# smart-switch.net
KiCad netlist of a schematic drawn in Altium Designer
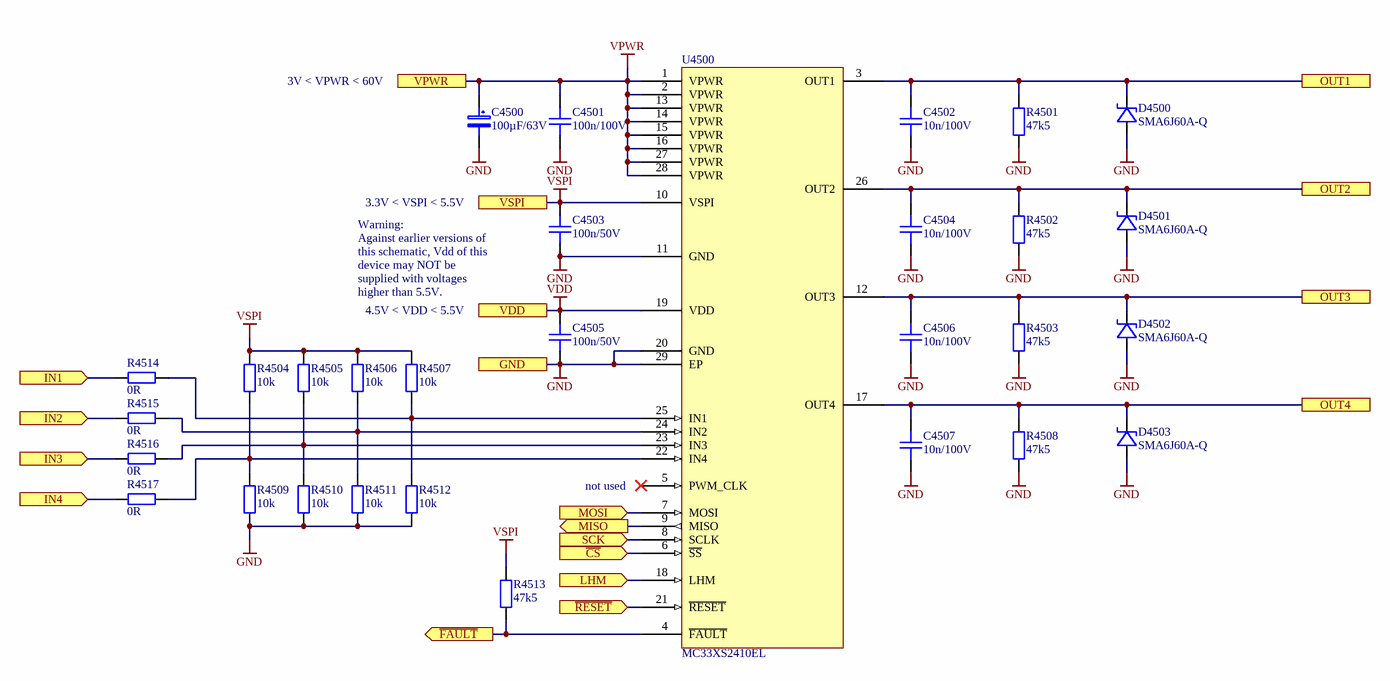
[diagram p0: smart-switch.SchDoc]

(export (version "E")
  (design (tool "Eeschema 10.0.6"))
  (components
    (comp (ref "C4500")
      (value "100µF/63V")
      (footprint "ELECTROLYTIC_CAP_PANASONIC_G")
      (description "SMD Electrolytic Capacitor")
      (fields (field (name "PART NUMBER") "EEE-TG1J101UP") (field (name "TOLERANCE") "+-20%"))
      (libsource (lib "OE750") (part "C_Pol"))
    )
    (comp (ref "C4501")
      (value "100n/100V")
      (footprint "CAPC1608X08N")
      (description "MLCC")
      (fields (field (name "PART NUMBER") "gen_C_ceramic_100n_100V_X7R_0603"))
      (libsource (lib "OE750") (part "C"))
    )
    (comp (ref "C4502")
      (value "10n/100V")
      (footprint "CAPC1608X08N")
      (description "MLCC")
      (fields (field (name "PART NUMBER") "gen_C_ceramic_10n_100V_X7R_0603"))
      (libsource (lib "OE750") (part "C"))
    )
    (comp (ref "C4503")
      (value "100n/50V")
      (footprint "CAPC1005X06N")
      (description "MLCC")
      (fields (field (name "PART NUMBER") "gen_C_ceramic_100n_50V_X7R_0402"))
      (libsource (lib "OE750") (part "C"))
    )
    (comp (ref "C4504")
      (value "10n/100V")
      (footprint "CAPC1608X08N")
      (description "MLCC")
      (fields (field (name "PART NUMBER") "gen_C_ceramic_10n_100V_X7R_0603"))
      (libsource (lib "OE750") (part "C"))
    )
    (comp (ref "C4505")
      (value "100n/50V")
      (footprint "CAPC1005X06N")
      (description "MLCC")
      (fields (field (name "PART NUMBER") "gen_C_ceramic_100n_50V_X7R_0402"))
      (libsource (lib "OE750") (part "C"))
    )
    (comp (ref "C4506")
      (value "10n/100V")
      (footprint "CAPC1608X08N")
      (description "MLCC")
      (fields (field (name "PART NUMBER") "gen_C_ceramic_10n_100V_X7R_0603"))
      (libsource (lib "OE750") (part "C"))
    )
    (comp (ref "C4507")
      (value "10n/100V")
      (footprint "CAPC1608X08N")
      (description "MLCC")
      (fields (field (name "PART NUMBER") "gen_C_ceramic_10n_100V_X7R_0603"))
      (libsource (lib "OE750") (part "C"))
    )
    (comp (ref "D4500")
      (value "SMA6J60A-Q")
      (footprint "BOURNS_DO-214AC_SMA")
      (description "TVS-Diode DO-214AC (SMA)")
      (fields (field (name "MANUFACTURER") "Bourns"))
      (libsource (lib "OE750") (part "D_TVS"))
    )
    (comp (ref "D4501")
      (value "SMA6J60A-Q")
      (footprint "BOURNS_DO-214AC_SMA")
      (description "TVS-Diode DO-214AC (SMA)")
      (fields (field (name "MANUFACTURER") "Bourns"))
      (libsource (lib "OE750") (part "D_TVS"))
    )
    (comp (ref "D4502")
      (value "SMA6J60A-Q")
      (footprint "BOURNS_DO-214AC_SMA")
      (description "TVS-Diode DO-214AC (SMA)")
      (fields (field (name "MANUFACTURER") "Bourns"))
      (libsource (lib "OE750") (part "D_TVS"))
    )
    (comp (ref "D4503")
      (value "SMA6J60A-Q")
      (footprint "BOURNS_DO-214AC_SMA")
      (description "TVS-Diode DO-214AC (SMA)")
      (fields (field (name "MANUFACTURER") "Bourns"))
      (libsource (lib "OE750") (part "D_TVS"))
    )
    (comp (ref "R4501")
      (value "47k5")
      (footprint "RESC1005X04N")
      (description "SMD Resistor 47k5 0402")
      (fields (field (name "PART NUMBER") "gen_R_47k5_0402") (field (name "TOLERANCE") "1%"))
      (libsource (lib "OE750") (part "R"))
    )
    (comp (ref "R4502")
      (value "47k5")
      (footprint "RESC1005X04N")
      (description "SMD Resistor 47k5 0402")
      (fields (field (name "PART NUMBER") "gen_R_47k5_0402") (field (name "TOLERANCE") "1%"))
      (libsource (lib "OE750") (part "R"))
    )
    (comp (ref "R4503")
      (value "47k5")
      (footprint "RESC1005X04N")
      (description "SMD Resistor 47k5 0402")
      (fields (field (name "PART NUMBER") "gen_R_47k5_0402") (field (name "TOLERANCE") "1%"))
      (libsource (lib "OE750") (part "R"))
    )
    (comp (ref "R4504")
      (value "10k")
      (footprint "RESC1005X04N")
      (description "SMD Resistor 10k 0402")
      (fields (field (name "PART NUMBER") "gen_R_10k_0402") (field (name "TOLERANCE") "1%"))
      (libsource (lib "OE750") (part "R"))
    )
    (comp (ref "R4505")
      (value "10k")
      (footprint "RESC1005X04N")
      (description "SMD Resistor 10k 0402")
      (fields (field (name "PART NUMBER") "gen_R_10k_0402") (field (name "TOLERANCE") "1%"))
      (libsource (lib "OE750") (part "R"))
    )
    (comp (ref "R4506")
      (value "10k")
      (footprint "RESC1005X04N")
      (description "SMD Resistor 10k 0402")
      (fields (field (name "PART NUMBER") "gen_R_10k_0402") (field (name "TOLERANCE") "1%"))
      (libsource (lib "OE750") (part "R"))
    )
    (comp (ref "R4507")
      (value "10k")
      (footprint "RESC1005X04N")
      (description "SMD Resistor 10k 0402")
      (fields (field (name "PART NUMBER") "gen_R_10k_0402") (field (name "TOLERANCE") "1%"))
      (libsource (lib "OE750") (part "R"))
    )
    (comp (ref "R4508")
      (value "47k5")
      (footprint "RESC1005X04N")
      (description "SMD Resistor 47k5 0402")
      (fields (field (name "PART NUMBER") "gen_R_47k5_0402") (field (name "TOLERANCE") "1%"))
      (libsource (lib "OE750") (part "R"))
    )
    (comp (ref "R4509")
      (value "10k")
      (footprint "RESC1005X04N")
      (description "SMD Resistor 10k 0402")
      (fields (field (name "PART NUMBER") "gen_R_10k_0402") (field (name "TOLERANCE") "1%"))
      (libsource (lib "OE750") (part "R"))
    )
    (comp (ref "R4510")
      (value "10k")
      (footprint "RESC1005X04N")
      (description "SMD Resistor 10k 0402")
      (fields (field (name "PART NUMBER") "gen_R_10k_0402") (field (name "TOLERANCE") "1%"))
      (libsource (lib "OE750") (part "R"))
    )
    (comp (ref "R4511")
      (value "10k")
      (footprint "RESC1005X04N")
      (description "SMD Resistor 10k 0402")
      (fields (field (name "PART NUMBER") "gen_R_10k_0402") (field (name "TOLERANCE") "1%"))
      (libsource (lib "OE750") (part "R"))
    )
    (comp (ref "R4512")
      (value "10k")
      (footprint "RESC1005X04N")
      (description "SMD Resistor 10k 0402")
      (fields (field (name "PART NUMBER") "gen_R_10k_0402") (field (name "TOLERANCE") "1%"))
      (libsource (lib "OE750") (part "R"))
    )
    (comp (ref "R4513")
      (value "47k5")
      (footprint "RESC1005X04N")
      (description "SMD Resistor 47k5 0402")
      (fields (field (name "PART NUMBER") "gen_R_47k5_0402") (field (name "TOLERANCE") "1%"))
      (libsource (lib "OE750") (part "R"))
    )
    (comp (ref "R4514")
      (value "0R")
      (footprint "RESC1005X04N")
      (description "SMD Resistor 0R 0402")
      (fields (field (name "PART NUMBER") "gen_R_0R_0402") (field (name "POWER") "0.063W"))
      (libsource (lib "OE750") (part "R"))
    )
    (comp (ref "R4515")
      (value "0R")
      (footprint "RESC1005X04N")
      (description "SMD Resistor 0R 0402")
      (fields (field (name "PART NUMBER") "gen_R_0R_0402") (field (name "POWER") "0.063W"))
      (libsource (lib "OE750") (part "R"))
    )
    (comp (ref "R4516")
      (value "0R")
      (footprint "RESC1005X04N")
      (description "SMD Resistor 0R 0402")
      (fields (field (name "PART NUMBER") "gen_R_0R_0402") (field (name "POWER") "0.063W"))
      (libsource (lib "OE750") (part "R"))
    )
    (comp (ref "R4517")
      (value "0R")
      (footprint "RESC1005X04N")
      (description "SMD Resistor 0R 0402")
      (fields (field (name "PART NUMBER") "gen_R_0R_0402") (field (name "POWER") "0.063W"))
      (libsource (lib "OE750") (part "R"))
    )
    (comp (ref "U4500")
      (value "MC33XS2410EL")
      (footprint "MC33XS2410EL")
      (description "Quad 100 mΩ / dual 50 mΩ, 3.0 V to 60 V high-side switch")
      (fields (field (name "MANUFACTURER") "NXP"))
      (libsource (lib "OE750") (part "MC33XS2410EL"))
    )
  )
  (nets
    (net (code "1") (name "/CS") (class "Default")
      (node (ref "U4500") (pin "6") (pinfunction "SS_6") (pintype "input"))
    )
    (net (code "2") (name "/FAULT") (class "Default")
      (node (ref "R4513") (pin "1") (pinfunction "1_1") (pintype "passive"))
      (node (ref "U4500") (pin "4") (pinfunction "FAULT_4") (pintype "open_collector"))
    )
    (net (code "3") (name "/IN1") (class "Default")
      (node (ref "R4514") (pin "1") (pinfunction "1_1") (pintype "passive"))
    )
    (net (code "4") (name "/IN2") (class "Default")
      (node (ref "R4515") (pin "1") (pinfunction "1_1") (pintype "passive"))
    )
    (net (code "5") (name "/IN3") (class "Default")
      (node (ref "R4516") (pin "1") (pinfunction "1_1") (pintype "passive"))
    )
    (net (code "6") (name "/IN4") (class "Default")
      (node (ref "R4517") (pin "1") (pinfunction "1_1") (pintype "passive"))
    )
    (net (code "7") (name "/LHM") (class "Default")
      (node (ref "U4500") (pin "18") (pinfunction "LHM_18") (pintype "input"))
    )
    (net (code "8") (name "/MISO") (class "Default")
      (node (ref "U4500") (pin "9") (pinfunction "MISO_9") (pintype "output"))
    )
    (net (code "9") (name "/MOSI") (class "Default")
      (node (ref "U4500") (pin "7") (pinfunction "MOSI_7") (pintype "input"))
    )
    (net (code "10") (name "/OUT1") (class "Default")
      (node (ref "C4502") (pin "2") (pinfunction "2_2") (pintype "passive"))
      (node (ref "D4500") (pin "1") (pinfunction "C_1") (pintype "passive"))
      (node (ref "R4501") (pin "2") (pinfunction "2_2") (pintype "passive"))
      (node (ref "U4500") (pin "3") (pinfunction "OUT1_3") (pintype "power_in"))
    )
    (net (code "11") (name "/OUT2") (class "Default")
      (node (ref "C4504") (pin "2") (pinfunction "2_2") (pintype "passive"))
      (node (ref "D4501") (pin "1") (pinfunction "C_1") (pintype "passive"))
      (node (ref "R4502") (pin "2") (pinfunction "2_2") (pintype "passive"))
      (node (ref "U4500") (pin "26") (pinfunction "OUT2_26") (pintype "power_in"))
    )
    (net (code "12") (name "/OUT3") (class "Default")
      (node (ref "C4506") (pin "2") (pinfunction "2_2") (pintype "passive"))
      (node (ref "D4502") (pin "1") (pinfunction "C_1") (pintype "passive"))
      (node (ref "R4503") (pin "2") (pinfunction "2_2") (pintype "passive"))
      (node (ref "U4500") (pin "12") (pinfunction "OUT3_12") (pintype "power_in"))
    )
    (net (code "13") (name "/OUT4") (class "Default")
      (node (ref "C4507") (pin "2") (pinfunction "2_2") (pintype "passive"))
      (node (ref "D4503") (pin "1") (pinfunction "C_1") (pintype "passive"))
      (node (ref "R4508") (pin "2") (pinfunction "2_2") (pintype "passive"))
      (node (ref "U4500") (pin "17") (pinfunction "OUT4_17") (pintype "power_in"))
    )
    (net (code "14") (name "/RESET") (class "Default")
      (node (ref "U4500") (pin "21") (pinfunction "RESET_21") (pintype "input"))
    )
    (net (code "15") (name "/SCK") (class "Default")
      (node (ref "U4500") (pin "8") (pinfunction "SCLK_8") (pintype "input"))
    )
    (net (code "16") (name "GND") (class "Default")
      (node (ref "C4500") (pin "2") (pinfunction "2_2") (pintype "passive"))
      (node (ref "C4501") (pin "1") (pinfunction "1_1") (pintype "passive"))
      (node (ref "C4502") (pin "1") (pinfunction "1_1") (pintype "passive"))
      (node (ref "C4503") (pin "1") (pinfunction "1_1") (pintype "passive"))
      (node (ref "C4504") (pin "1") (pinfunction "1_1") (pintype "passive"))
      (node (ref "C4505") (pin "1") (pinfunction "1_1") (pintype "passive"))
      (node (ref "C4506") (pin "1") (pinfunction "1_1") (pintype "passive"))
      (node (ref "C4507") (pin "1") (pinfunction "1_1") (pintype "passive"))
      (node (ref "D4500") (pin "2") (pinfunction "A_2") (pintype "passive"))
      (node (ref "D4501") (pin "2") (pinfunction "A_2") (pintype "passive"))
      (node (ref "D4502") (pin "2") (pinfunction "A_2") (pintype "passive"))
      (node (ref "D4503") (pin "2") (pinfunction "A_2") (pintype "passive"))
      (node (ref "R4501") (pin "1") (pinfunction "1_1") (pintype "passive"))
      (node (ref "R4502") (pin "1") (pinfunction "1_1") (pintype "passive"))
      (node (ref "R4503") (pin "1") (pinfunction "1_1") (pintype "passive"))
      (node (ref "R4508") (pin "1") (pinfunction "1_1") (pintype "passive"))
      (node (ref "R4509") (pin "1") (pinfunction "1_1") (pintype "passive"))
      (node (ref "R4510") (pin "1") (pinfunction "1_1") (pintype "passive"))
      (node (ref "R4511") (pin "1") (pinfunction "1_1") (pintype "passive"))
      (node (ref "R4512") (pin "1") (pinfunction "1_1") (pintype "passive"))
      (node (ref "U4500") (pin "11") (pinfunction "GND_11") (pintype "power_in"))
      (node (ref "U4500") (pin "20") (pinfunction "GND_20") (pintype "power_in"))
      (node (ref "U4500") (pin "29") (pinfunction "EP_29") (pintype "power_in"))
    )
    (net (code "17") (name "Net-(U4500-IN1)") (class "Default")
      (node (ref "R4507") (pin "1") (pinfunction "1_1") (pintype "passive"))
      (node (ref "R4512") (pin "2") (pinfunction "2_2") (pintype "passive"))
      (node (ref "R4514") (pin "2") (pinfunction "2_2") (pintype "passive"))
      (node (ref "U4500") (pin "25") (pinfunction "IN1_25") (pintype "input"))
    )
    (net (code "18") (name "Net-(U4500-IN2)") (class "Default")
      (node (ref "R4506") (pin "1") (pinfunction "1_1") (pintype "passive"))
      (node (ref "R4511") (pin "2") (pinfunction "2_2") (pintype "passive"))
      (node (ref "R4515") (pin "2") (pinfunction "2_2") (pintype "passive"))
      (node (ref "U4500") (pin "24") (pinfunction "IN2_24") (pintype "input"))
    )
    (net (code "19") (name "Net-(U4500-IN3)") (class "Default")
      (node (ref "R4505") (pin "1") (pinfunction "1_1") (pintype "passive"))
      (node (ref "R4510") (pin "2") (pinfunction "2_2") (pintype "passive"))
      (node (ref "R4516") (pin "2") (pinfunction "2_2") (pintype "passive"))
      (node (ref "U4500") (pin "23") (pinfunction "IN3_23") (pintype "input"))
    )
    (net (code "20") (name "Net-(U4500-IN4)") (class "Default")
      (node (ref "R4504") (pin "1") (pinfunction "1_1") (pintype "passive"))
      (node (ref "R4509") (pin "2") (pinfunction "2_2") (pintype "passive"))
      (node (ref "R4517") (pin "2") (pinfunction "2_2") (pintype "passive"))
      (node (ref "U4500") (pin "22") (pinfunction "IN4_22") (pintype "input"))
    )
    (net (code "21") (name "VDD") (class "Default")
      (node (ref "C4505") (pin "2") (pinfunction "2_2") (pintype "passive"))
      (node (ref "U4500") (pin "19") (pinfunction "VDD_19") (pintype "power_in"))
    )
    (net (code "22") (name "VPWR") (class "Default")
      (node (ref "C4500") (pin "1") (pinfunction "1_1") (pintype "passive"))
      (node (ref "C4501") (pin "2") (pinfunction "2_2") (pintype "passive"))
      (node (ref "U4500") (pin "1") (pinfunction "VPWR_1") (pintype "power_in"))
      (node (ref "U4500") (pin "13") (pinfunction "VPWR_13") (pintype "power_in"))
      (node (ref "U4500") (pin "14") (pinfunction "VPWR_14") (pintype "power_in"))
      (node (ref "U4500") (pin "15") (pinfunction "VPWR_15") (pintype "power_in"))
      (node (ref "U4500") (pin "16") (pinfunction "VPWR_16") (pintype "power_in"))
      (node (ref "U4500") (pin "2") (pinfunction "VPWR_2") (pintype "power_in"))
      (node (ref "U4500") (pin "27") (pinfunction "VPWR_27") (pintype "power_in"))
      (node (ref "U4500") (pin "28") (pinfunction "VPWR_28") (pintype "power_in"))
    )
    (net (code "23") (name "VSPI") (class "Default")
      (node (ref "C4503") (pin "2") (pinfunction "2_2") (pintype "passive"))
      (node (ref "R4504") (pin "2") (pinfunction "2_2") (pintype "passive"))
      (node (ref "R4505") (pin "2") (pinfunction "2_2") (pintype "passive"))
      (node (ref "R4506") (pin "2") (pinfunction "2_2") (pintype "passive"))
      (node (ref "R4507") (pin "2") (pinfunction "2_2") (pintype "passive"))
      (node (ref "R4513") (pin "2") (pinfunction "2_2") (pintype "passive"))
      (node (ref "U4500") (pin "10") (pinfunction "VSPI_10") (pintype "power_in"))
    )
    (net (code "24") (name "unconnected-(U4500-PWM_CLK-Pad5)") (class "Default")
      (node (ref "U4500") (pin "5") (pinfunction "PWM_CLK_5") (pintype "input+no_connect"))
    )
  )
)
